# ProtoPass.net
KiCad netlist of a schematic drawn in EAGLE
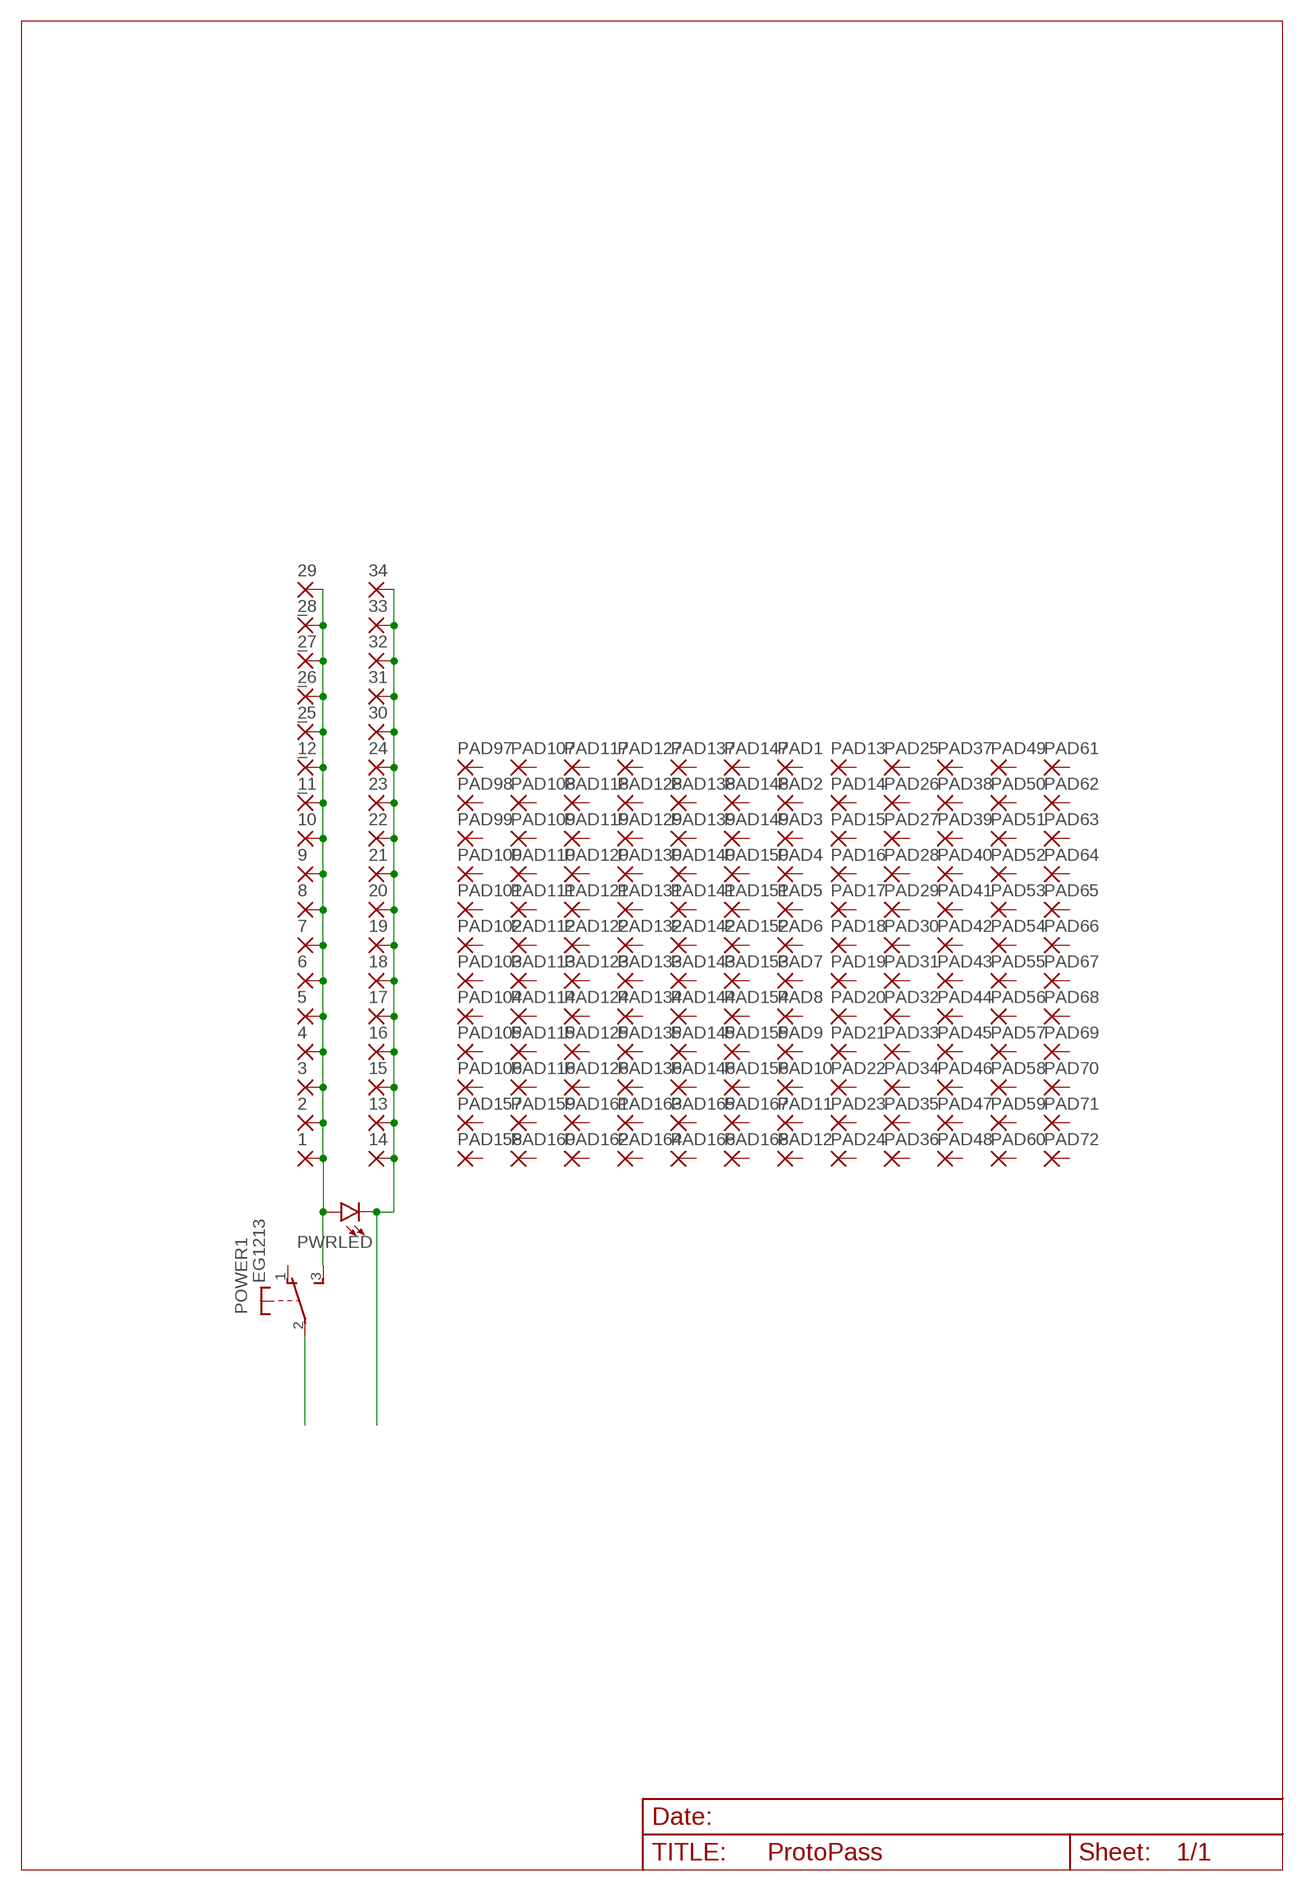
[diagram p0: schematic, sheet 1]

(export (version "E")
  (design (tool "Eeschema 10.0.6"))
  (components
    (comp (ref "1")
      (value "1,6/0,9")
      (footprint "eagle-import:1,6_0,9")
      (libsource (lib "eagle-import") (part "1,6/0,9"))
    )
    (comp (ref "2")
      (value "1,6/0,9")
      (footprint "eagle-import:1,6_0,9")
      (libsource (lib "eagle-import") (part "1,6/0,9"))
    )
    (comp (ref "3")
      (value "1,6/0,9")
      (footprint "eagle-import:1,6_0,9")
      (libsource (lib "eagle-import") (part "1,6/0,9"))
    )
    (comp (ref "4")
      (value "1,6/0,9")
      (footprint "eagle-import:1,6_0,9")
      (libsource (lib "eagle-import") (part "1,6/0,9"))
    )
    (comp (ref "5")
      (value "1,6/0,9")
      (footprint "eagle-import:1,6_0,9")
      (libsource (lib "eagle-import") (part "1,6/0,9"))
    )
    (comp (ref "6")
      (value "1,6/0,9")
      (footprint "eagle-import:1,6_0,9")
      (libsource (lib "eagle-import") (part "1,6/0,9"))
    )
    (comp (ref "7")
      (value "1,6/0,9")
      (footprint "eagle-import:1,6_0,9")
      (libsource (lib "eagle-import") (part "1,6/0,9"))
    )
    (comp (ref "8")
      (value "1,6/0,9")
      (footprint "eagle-import:1,6_0,9")
      (libsource (lib "eagle-import") (part "1,6/0,9"))
    )
    (comp (ref "9")
      (value "1,6/0,9")
      (footprint "eagle-import:1,6_0,9")
      (libsource (lib "eagle-import") (part "1,6/0,9"))
    )
    (comp (ref "10")
      (value "1,6/0,9")
      (footprint "eagle-import:1,6_0,9")
      (libsource (lib "eagle-import") (part "1,6/0,9"))
    )
    (comp (ref "11")
      (value "1,6/0,9")
      (footprint "eagle-import:1,6_0,9")
      (libsource (lib "eagle-import") (part "1,6/0,9"))
    )
    (comp (ref "12")
      (value "_")
      (footprint "eagle-import:1,6_0,9")
      (libsource (lib "eagle-import") (part "1,6/0,9"))
    )
    (comp (ref "13")
      (value "1,6/0,9")
      (footprint "eagle-import:1,6_0,9")
      (libsource (lib "eagle-import") (part "1,6/0,9"))
    )
    (comp (ref "14")
      (value "1,6/0,9")
      (footprint "eagle-import:1,6_0,9")
      (libsource (lib "eagle-import") (part "1,6/0,9"))
    )
    (comp (ref "15")
      (value "1,6/0,9")
      (footprint "eagle-import:1,6_0,9")
      (libsource (lib "eagle-import") (part "1,6/0,9"))
    )
    (comp (ref "16")
      (value "1,6/0,9")
      (footprint "eagle-import:1,6_0,9")
      (libsource (lib "eagle-import") (part "1,6/0,9"))
    )
    (comp (ref "17")
      (value "1,6/0,9")
      (footprint "eagle-import:1,6_0,9")
      (libsource (lib "eagle-import") (part "1,6/0,9"))
    )
    (comp (ref "18")
      (value "1,6/0,9")
      (footprint "eagle-import:1,6_0,9")
      (libsource (lib "eagle-import") (part "1,6/0,9"))
    )
    (comp (ref "19")
      (value "1,6/0,9")
      (footprint "eagle-import:1,6_0,9")
      (libsource (lib "eagle-import") (part "1,6/0,9"))
    )
    (comp (ref "20")
      (value "1,6/0,9")
      (footprint "eagle-import:1,6_0,9")
      (libsource (lib "eagle-import") (part "1,6/0,9"))
    )
    (comp (ref "21")
      (value "1,6/0,9")
      (footprint "eagle-import:1,6_0,9")
      (libsource (lib "eagle-import") (part "1,6/0,9"))
    )
    (comp (ref "22")
      (value "1,6/0,9")
      (footprint "eagle-import:1,6_0,9")
      (libsource (lib "eagle-import") (part "1,6/0,9"))
    )
    (comp (ref "23")
      (value "1,6/0,9")
      (footprint "eagle-import:1,6_0,9")
      (libsource (lib "eagle-import") (part "1,6/0,9"))
    )
    (comp (ref "24")
      (value "1,6/0,9")
      (footprint "eagle-import:1,6_0,9")
      (libsource (lib "eagle-import") (part "1,6/0,9"))
    )
    (comp (ref "25")
      (value "_")
      (footprint "eagle-import:1,6_0,9")
      (libsource (lib "eagle-import") (part "1,6/0,9"))
    )
    (comp (ref "26")
      (value "_")
      (footprint "eagle-import:1,6_0,9")
      (libsource (lib "eagle-import") (part "1,6/0,9"))
    )
    (comp (ref "27")
      (value "_")
      (footprint "eagle-import:1,6_0,9")
      (libsource (lib "eagle-import") (part "1,6/0,9"))
    )
    (comp (ref "28")
      (value "_")
      (footprint "eagle-import:1,6_0,9")
      (libsource (lib "eagle-import") (part "1,6/0,9"))
    )
    (comp (ref "29")
      (value "_")
      (footprint "eagle-import:1,6_0,9")
      (libsource (lib "eagle-import") (part "1,6/0,9"))
    )
    (comp (ref "30")
      (value "1,6/0,9")
      (footprint "eagle-import:1,6_0,9")
      (libsource (lib "eagle-import") (part "1,6/0,9"))
    )
    (comp (ref "31")
      (value "1,6/0,9")
      (footprint "eagle-import:1,6_0,9")
      (libsource (lib "eagle-import") (part "1,6/0,9"))
    )
    (comp (ref "32")
      (value "1,6/0,9")
      (footprint "eagle-import:1,6_0,9")
      (libsource (lib "eagle-import") (part "1,6/0,9"))
    )
    (comp (ref "33")
      (value "1,6/0,9")
      (footprint "eagle-import:1,6_0,9")
      (libsource (lib "eagle-import") (part "1,6/0,9"))
    )
    (comp (ref "34")
      (value "1,6/0,9")
      (footprint "eagle-import:1,6_0,9")
      (libsource (lib "eagle-import") (part "1,6/0,9"))
    )
    (comp (ref "PAD1")
      (value "1,6/0,9")
      (footprint "eagle-import:1,6_0,9")
      (libsource (lib "eagle-import") (part "1,6/0,9"))
    )
    (comp (ref "PAD2")
      (value "1,6/0,9")
      (footprint "eagle-import:1,6_0,9")
      (libsource (lib "eagle-import") (part "1,6/0,9"))
    )
    (comp (ref "PAD3")
      (value "1,6/0,9")
      (footprint "eagle-import:1,6_0,9")
      (libsource (lib "eagle-import") (part "1,6/0,9"))
    )
    (comp (ref "PAD4")
      (value "1,6/0,9")
      (footprint "eagle-import:1,6_0,9")
      (libsource (lib "eagle-import") (part "1,6/0,9"))
    )
    (comp (ref "PAD5")
      (value "1,6/0,9")
      (footprint "eagle-import:1,6_0,9")
      (libsource (lib "eagle-import") (part "1,6/0,9"))
    )
    (comp (ref "PAD6")
      (value "1,6/0,9")
      (footprint "eagle-import:1,6_0,9")
      (libsource (lib "eagle-import") (part "1,6/0,9"))
    )
    (comp (ref "PAD7")
      (value "1,6/0,9")
      (footprint "eagle-import:1,6_0,9")
      (libsource (lib "eagle-import") (part "1,6/0,9"))
    )
    (comp (ref "PAD8")
      (value "1,6/0,9")
      (footprint "eagle-import:1,6_0,9")
      (libsource (lib "eagle-import") (part "1,6/0,9"))
    )
    (comp (ref "PAD9")
      (value "1,6/0,9")
      (footprint "eagle-import:1,6_0,9")
      (libsource (lib "eagle-import") (part "1,6/0,9"))
    )
    (comp (ref "PAD10")
      (value "1,6/0,9")
      (footprint "eagle-import:1,6_0,9")
      (libsource (lib "eagle-import") (part "1,6/0,9"))
    )
    (comp (ref "PAD11")
      (value "1,6/0,9")
      (footprint "eagle-import:1,6_0,9")
      (libsource (lib "eagle-import") (part "1,6/0,9"))
    )
    (comp (ref "PAD12")
      (value "1,6/0,9")
      (footprint "eagle-import:1,6_0,9")
      (libsource (lib "eagle-import") (part "1,6/0,9"))
    )
    (comp (ref "PAD13")
      (value "1,6/0,9")
      (footprint "eagle-import:1,6_0,9")
      (libsource (lib "eagle-import") (part "1,6/0,9"))
    )
    (comp (ref "PAD14")
      (value "1,6/0,9")
      (footprint "eagle-import:1,6_0,9")
      (libsource (lib "eagle-import") (part "1,6/0,9"))
    )
    (comp (ref "PAD15")
      (value "1,6/0,9")
      (footprint "eagle-import:1,6_0,9")
      (libsource (lib "eagle-import") (part "1,6/0,9"))
    )
    (comp (ref "PAD16")
      (value "1,6/0,9")
      (footprint "eagle-import:1,6_0,9")
      (libsource (lib "eagle-import") (part "1,6/0,9"))
    )
    (comp (ref "PAD17")
      (value "1,6/0,9")
      (footprint "eagle-import:1,6_0,9")
      (libsource (lib "eagle-import") (part "1,6/0,9"))
    )
    (comp (ref "PAD18")
      (value "1,6/0,9")
      (footprint "eagle-import:1,6_0,9")
      (libsource (lib "eagle-import") (part "1,6/0,9"))
    )
    (comp (ref "PAD19")
      (value "1,6/0,9")
      (footprint "eagle-import:1,6_0,9")
      (libsource (lib "eagle-import") (part "1,6/0,9"))
    )
    (comp (ref "PAD20")
      (value "1,6/0,9")
      (footprint "eagle-import:1,6_0,9")
      (libsource (lib "eagle-import") (part "1,6/0,9"))
    )
    (comp (ref "PAD21")
      (value "1,6/0,9")
      (footprint "eagle-import:1,6_0,9")
      (libsource (lib "eagle-import") (part "1,6/0,9"))
    )
    (comp (ref "PAD22")
      (value "1,6/0,9")
      (footprint "eagle-import:1,6_0,9")
      (libsource (lib "eagle-import") (part "1,6/0,9"))
    )
    (comp (ref "PAD23")
      (value "1,6/0,9")
      (footprint "eagle-import:1,6_0,9")
      (libsource (lib "eagle-import") (part "1,6/0,9"))
    )
    (comp (ref "PAD24")
      (value "1,6/0,9")
      (footprint "eagle-import:1,6_0,9")
      (libsource (lib "eagle-import") (part "1,6/0,9"))
    )
    (comp (ref "PAD25")
      (value "1,6/0,9")
      (footprint "eagle-import:1,6_0,9")
      (libsource (lib "eagle-import") (part "1,6/0,9"))
    )
    (comp (ref "PAD26")
      (value "1,6/0,9")
      (footprint "eagle-import:1,6_0,9")
      (libsource (lib "eagle-import") (part "1,6/0,9"))
    )
    (comp (ref "PAD27")
      (value "1,6/0,9")
      (footprint "eagle-import:1,6_0,9")
      (libsource (lib "eagle-import") (part "1,6/0,9"))
    )
    (comp (ref "PAD28")
      (value "1,6/0,9")
      (footprint "eagle-import:1,6_0,9")
      (libsource (lib "eagle-import") (part "1,6/0,9"))
    )
    (comp (ref "PAD29")
      (value "1,6/0,9")
      (footprint "eagle-import:1,6_0,9")
      (libsource (lib "eagle-import") (part "1,6/0,9"))
    )
    (comp (ref "PAD30")
      (value "1,6/0,9")
      (footprint "eagle-import:1,6_0,9")
      (libsource (lib "eagle-import") (part "1,6/0,9"))
    )
    (comp (ref "PAD31")
      (value "1,6/0,9")
      (footprint "eagle-import:1,6_0,9")
      (libsource (lib "eagle-import") (part "1,6/0,9"))
    )
    (comp (ref "PAD32")
      (value "1,6/0,9")
      (footprint "eagle-import:1,6_0,9")
      (libsource (lib "eagle-import") (part "1,6/0,9"))
    )
    (comp (ref "PAD33")
      (value "1,6/0,9")
      (footprint "eagle-import:1,6_0,9")
      (libsource (lib "eagle-import") (part "1,6/0,9"))
    )
    (comp (ref "PAD34")
      (value "1,6/0,9")
      (footprint "eagle-import:1,6_0,9")
      (libsource (lib "eagle-import") (part "1,6/0,9"))
    )
    (comp (ref "PAD35")
      (value "1,6/0,9")
      (footprint "eagle-import:1,6_0,9")
      (libsource (lib "eagle-import") (part "1,6/0,9"))
    )
    (comp (ref "PAD36")
      (value "1,6/0,9")
      (footprint "eagle-import:1,6_0,9")
      (libsource (lib "eagle-import") (part "1,6/0,9"))
    )
    (comp (ref "PAD37")
      (value "1,6/0,9")
      (footprint "eagle-import:1,6_0,9")
      (libsource (lib "eagle-import") (part "1,6/0,9"))
    )
    (comp (ref "PAD38")
      (value "1,6/0,9")
      (footprint "eagle-import:1,6_0,9")
      (libsource (lib "eagle-import") (part "1,6/0,9"))
    )
    (comp (ref "PAD39")
      (value "1,6/0,9")
      (footprint "eagle-import:1,6_0,9")
      (libsource (lib "eagle-import") (part "1,6/0,9"))
    )
    (comp (ref "PAD40")
      (value "1,6/0,9")
      (footprint "eagle-import:1,6_0,9")
      (libsource (lib "eagle-import") (part "1,6/0,9"))
    )
    (comp (ref "PAD41")
      (value "1,6/0,9")
      (footprint "eagle-import:1,6_0,9")
      (libsource (lib "eagle-import") (part "1,6/0,9"))
    )
    (comp (ref "PAD42")
      (value "1,6/0,9")
      (footprint "eagle-import:1,6_0,9")
      (libsource (lib "eagle-import") (part "1,6/0,9"))
    )
    (comp (ref "PAD43")
      (value "1,6/0,9")
      (footprint "eagle-import:1,6_0,9")
      (libsource (lib "eagle-import") (part "1,6/0,9"))
    )
    (comp (ref "PAD44")
      (value "1,6/0,9")
      (footprint "eagle-import:1,6_0,9")
      (libsource (lib "eagle-import") (part "1,6/0,9"))
    )
    (comp (ref "PAD45")
      (value "1,6/0,9")
      (footprint "eagle-import:1,6_0,9")
      (libsource (lib "eagle-import") (part "1,6/0,9"))
    )
    (comp (ref "PAD46")
      (value "1,6/0,9")
      (footprint "eagle-import:1,6_0,9")
      (libsource (lib "eagle-import") (part "1,6/0,9"))
    )
    (comp (ref "PAD47")
      (value "1,6/0,9")
      (footprint "eagle-import:1,6_0,9")
      (libsource (lib "eagle-import") (part "1,6/0,9"))
    )
    (comp (ref "PAD48")
      (value "1,6/0,9")
      (footprint "eagle-import:1,6_0,9")
      (libsource (lib "eagle-import") (part "1,6/0,9"))
    )
    (comp (ref "PAD49")
      (value "1,6/0,9")
      (footprint "eagle-import:1,6_0,9")
      (libsource (lib "eagle-import") (part "1,6/0,9"))
    )
    (comp (ref "PAD50")
      (value "1,6/0,9")
      (footprint "eagle-import:1,6_0,9")
      (libsource (lib "eagle-import") (part "1,6/0,9"))
    )
    (comp (ref "PAD51")
      (value "1,6/0,9")
      (footprint "eagle-import:1,6_0,9")
      (libsource (lib "eagle-import") (part "1,6/0,9"))
    )
    (comp (ref "PAD52")
      (value "1,6/0,9")
      (footprint "eagle-import:1,6_0,9")
      (libsource (lib "eagle-import") (part "1,6/0,9"))
    )
    (comp (ref "PAD53")
      (value "1,6/0,9")
      (footprint "eagle-import:1,6_0,9")
      (libsource (lib "eagle-import") (part "1,6/0,9"))
    )
    (comp (ref "PAD54")
      (value "1,6/0,9")
      (footprint "eagle-import:1,6_0,9")
      (libsource (lib "eagle-import") (part "1,6/0,9"))
    )
    (comp (ref "PAD55")
      (value "1,6/0,9")
      (footprint "eagle-import:1,6_0,9")
      (libsource (lib "eagle-import") (part "1,6/0,9"))
    )
    (comp (ref "PAD56")
      (value "1,6/0,9")
      (footprint "eagle-import:1,6_0,9")
      (libsource (lib "eagle-import") (part "1,6/0,9"))
    )
    (comp (ref "PAD57")
      (value "1,6/0,9")
      (footprint "eagle-import:1,6_0,9")
      (libsource (lib "eagle-import") (part "1,6/0,9"))
    )
    (comp (ref "PAD58")
      (value "1,6/0,9")
      (footprint "eagle-import:1,6_0,9")
      (libsource (lib "eagle-import") (part "1,6/0,9"))
    )
    (comp (ref "PAD59")
      (value "1,6/0,9")
      (footprint "eagle-import:1,6_0,9")
      (libsource (lib "eagle-import") (part "1,6/0,9"))
    )
    (comp (ref "PAD60")
      (value "1,6/0,9")
      (footprint "eagle-import:1,6_0,9")
      (libsource (lib "eagle-import") (part "1,6/0,9"))
    )
    (comp (ref "PAD61")
      (value "1,6/0,9")
      (footprint "eagle-import:1,6_0,9")
      (libsource (lib "eagle-import") (part "1,6/0,9"))
    )
    (comp (ref "PAD62")
      (value "1,6/0,9")
      (footprint "eagle-import:1,6_0,9")
      (libsource (lib "eagle-import") (part "1,6/0,9"))
    )
    (comp (ref "PAD63")
      (value "1,6/0,9")
      (footprint "eagle-import:1,6_0,9")
      (libsource (lib "eagle-import") (part "1,6/0,9"))
    )
    (comp (ref "PAD64")
      (value "1,6/0,9")
      (footprint "eagle-import:1,6_0,9")
      (libsource (lib "eagle-import") (part "1,6/0,9"))
    )
    (comp (ref "PAD65")
      (value "1,6/0,9")
      (footprint "eagle-import:1,6_0,9")
      (libsource (lib "eagle-import") (part "1,6/0,9"))
    )
    (comp (ref "PAD66")
      (value "1,6/0,9")
      (footprint "eagle-import:1,6_0,9")
      (libsource (lib "eagle-import") (part "1,6/0,9"))
    )
    (comp (ref "PAD67")
      (value "1,6/0,9")
      (footprint "eagle-import:1,6_0,9")
      (libsource (lib "eagle-import") (part "1,6/0,9"))
    )
    (comp (ref "PAD68")
      (value "1,6/0,9")
      (footprint "eagle-import:1,6_0,9")
      (libsource (lib "eagle-import") (part "1,6/0,9"))
    )
    (comp (ref "PAD69")
      (value "1,6/0,9")
      (footprint "eagle-import:1,6_0,9")
      (libsource (lib "eagle-import") (part "1,6/0,9"))
    )
    (comp (ref "PAD70")
      (value "1,6/0,9")
      (footprint "eagle-import:1,6_0,9")
      (libsource (lib "eagle-import") (part "1,6/0,9"))
    )
    (comp (ref "PAD71")
      (value "1,6/0,9")
      (footprint "eagle-import:1,6_0,9")
      (libsource (lib "eagle-import") (part "1,6/0,9"))
    )
    (comp (ref "PAD72")
      (value "1,6/0,9")
      (footprint "eagle-import:1,6_0,9")
      (libsource (lib "eagle-import") (part "1,6/0,9"))
    )
    (comp (ref "PAD97")
      (value "1,6/0,9")
      (footprint "eagle-import:1,6_0,9")
      (libsource (lib "eagle-import") (part "1,6/0,9"))
    )
    (comp (ref "PAD98")
      (value "1,6/0,9")
      (footprint "eagle-import:1,6_0,9")
      (libsource (lib "eagle-import") (part "1,6/0,9"))
    )
    (comp (ref "PAD99")
      (value "1,6/0,9")
      (footprint "eagle-import:1,6_0,9")
      (libsource (lib "eagle-import") (part "1,6/0,9"))
    )
    (comp (ref "PAD100")
      (value "1,6/0,9")
      (footprint "eagle-import:1,6_0,9")
      (libsource (lib "eagle-import") (part "1,6/0,9"))
    )
    (comp (ref "PAD101")
      (value "1,6/0,9")
      (footprint "eagle-import:1,6_0,9")
      (libsource (lib "eagle-import") (part "1,6/0,9"))
    )
    (comp (ref "PAD102")
      (value "1,6/0,9")
      (footprint "eagle-import:1,6_0,9")
      (libsource (lib "eagle-import") (part "1,6/0,9"))
    )
    (comp (ref "PAD103")
      (value "1,6/0,9")
      (footprint "eagle-import:1,6_0,9")
      (libsource (lib "eagle-import") (part "1,6/0,9"))
    )
    (comp (ref "PAD104")
      (value "1,6/0,9")
      (footprint "eagle-import:1,6_0,9")
      (libsource (lib "eagle-import") (part "1,6/0,9"))
    )
    (comp (ref "PAD105")
      (value "1,6/0,9")
      (footprint "eagle-import:1,6_0,9")
      (libsource (lib "eagle-import") (part "1,6/0,9"))
    )
    (comp (ref "PAD106")
      (value "1,6/0,9")
      (footprint "eagle-import:1,6_0,9")
      (libsource (lib "eagle-import") (part "1,6/0,9"))
    )
    (comp (ref "PAD107")
      (value "1,6/0,9")
      (footprint "eagle-import:1,6_0,9")
      (libsource (lib "eagle-import") (part "1,6/0,9"))
    )
    (comp (ref "PAD108")
      (value "1,6/0,9")
      (footprint "eagle-import:1,6_0,9")
      (libsource (lib "eagle-import") (part "1,6/0,9"))
    )
    (comp (ref "PAD109")
      (value "1,6/0,9")
      (footprint "eagle-import:1,6_0,9")
      (libsource (lib "eagle-import") (part "1,6/0,9"))
    )
    (comp (ref "PAD110")
      (value "1,6/0,9")
      (footprint "eagle-import:1,6_0,9")
      (libsource (lib "eagle-import") (part "1,6/0,9"))
    )
    (comp (ref "PAD111")
      (value "1,6/0,9")
      (footprint "eagle-import:1,6_0,9")
      (libsource (lib "eagle-import") (part "1,6/0,9"))
    )
    (comp (ref "PAD112")
      (value "1,6/0,9")
      (footprint "eagle-import:1,6_0,9")
      (libsource (lib "eagle-import") (part "1,6/0,9"))
    )
    (comp (ref "PAD113")
      (value "1,6/0,9")
      (footprint "eagle-import:1,6_0,9")
      (libsource (lib "eagle-import") (part "1,6/0,9"))
    )
    (comp (ref "PAD114")
      (value "1,6/0,9")
      (footprint "eagle-import:1,6_0,9")
      (libsource (lib "eagle-import") (part "1,6/0,9"))
    )
    (comp (ref "PAD115")
      (value "1,6/0,9")
      (footprint "eagle-import:1,6_0,9")
      (libsource (lib "eagle-import") (part "1,6/0,9"))
    )
    (comp (ref "PAD116")
      (value "1,6/0,9")
      (footprint "eagle-import:1,6_0,9")
      (libsource (lib "eagle-import") (part "1,6/0,9"))
    )
    (comp (ref "PAD117")
      (value "1,6/0,9")
      (footprint "eagle-import:1,6_0,9")
      (libsource (lib "eagle-import") (part "1,6/0,9"))
    )
    (comp (ref "PAD118")
      (value "1,6/0,9")
      (footprint "eagle-import:1,6_0,9")
      (libsource (lib "eagle-import") (part "1,6/0,9"))
    )
    (comp (ref "PAD119")
      (value "1,6/0,9")
      (footprint "eagle-import:1,6_0,9")
      (libsource (lib "eagle-import") (part "1,6/0,9"))
    )
    (comp (ref "PAD120")
      (value "1,6/0,9")
      (footprint "eagle-import:1,6_0,9")
      (libsource (lib "eagle-import") (part "1,6/0,9"))
    )
    (comp (ref "PAD121")
      (value "1,6/0,9")
      (footprint "eagle-import:1,6_0,9")
      (libsource (lib "eagle-import") (part "1,6/0,9"))
    )
    (comp (ref "PAD122")
      (value "1,6/0,9")
      (footprint "eagle-import:1,6_0,9")
      (libsource (lib "eagle-import") (part "1,6/0,9"))
    )
    (comp (ref "PAD123")
      (value "1,6/0,9")
      (footprint "eagle-import:1,6_0,9")
      (libsource (lib "eagle-import") (part "1,6/0,9"))
    )
    (comp (ref "PAD124")
      (value "1,6/0,9")
      (footprint "eagle-import:1,6_0,9")
      (libsource (lib "eagle-import") (part "1,6/0,9"))
    )
    (comp (ref "PAD125")
      (value "1,6/0,9")
      (footprint "eagle-import:1,6_0,9")
      (libsource (lib "eagle-import") (part "1,6/0,9"))
    )
    (comp (ref "PAD126")
      (value "1,6/0,9")
      (footprint "eagle-import:1,6_0,9")
      (libsource (lib "eagle-import") (part "1,6/0,9"))
    )
    (comp (ref "PAD127")
      (value "1,6/0,9")
      (footprint "eagle-import:1,6_0,9")
      (libsource (lib "eagle-import") (part "1,6/0,9"))
    )
    (comp (ref "PAD128")
      (value "1,6/0,9")
      (footprint "eagle-import:1,6_0,9")
      (libsource (lib "eagle-import") (part "1,6/0,9"))
    )
    (comp (ref "PAD129")
      (value "1,6/0,9")
      (footprint "eagle-import:1,6_0,9")
      (libsource (lib "eagle-import") (part "1,6/0,9"))
    )
    (comp (ref "PAD130")
      (value "1,6/0,9")
      (footprint "eagle-import:1,6_0,9")
      (libsource (lib "eagle-import") (part "1,6/0,9"))
    )
    (comp (ref "PAD131")
      (value "1,6/0,9")
      (footprint "eagle-import:1,6_0,9")
      (libsource (lib "eagle-import") (part "1,6/0,9"))
    )
    (comp (ref "PAD132")
      (value "1,6/0,9")
      (footprint "eagle-import:1,6_0,9")
      (libsource (lib "eagle-import") (part "1,6/0,9"))
    )
    (comp (ref "PAD133")
      (value "1,6/0,9")
      (footprint "eagle-import:1,6_0,9")
      (libsource (lib "eagle-import") (part "1,6/0,9"))
    )
    (comp (ref "PAD134")
      (value "1,6/0,9")
      (footprint "eagle-import:1,6_0,9")
      (libsource (lib "eagle-import") (part "1,6/0,9"))
    )
    (comp (ref "PAD135")
      (value "1,6/0,9")
      (footprint "eagle-import:1,6_0,9")
      (libsource (lib "eagle-import") (part "1,6/0,9"))
    )
    (comp (ref "PAD136")
      (value "1,6/0,9")
      (footprint "eagle-import:1,6_0,9")
      (libsource (lib "eagle-import") (part "1,6/0,9"))
    )
    (comp (ref "PAD137")
      (value "1,6/0,9")
      (footprint "eagle-import:1,6_0,9")
      (libsource (lib "eagle-import") (part "1,6/0,9"))
    )
    (comp (ref "PAD138")
      (value "1,6/0,9")
      (footprint "eagle-import:1,6_0,9")
      (libsource (lib "eagle-import") (part "1,6/0,9"))
    )
    (comp (ref "PAD139")
      (value "1,6/0,9")
      (footprint "eagle-import:1,6_0,9")
      (libsource (lib "eagle-import") (part "1,6/0,9"))
    )
    (comp (ref "PAD140")
      (value "1,6/0,9")
      (footprint "eagle-import:1,6_0,9")
      (libsource (lib "eagle-import") (part "1,6/0,9"))
    )
    (comp (ref "PAD141")
      (value "1,6/0,9")
      (footprint "eagle-import:1,6_0,9")
      (libsource (lib "eagle-import") (part "1,6/0,9"))
    )
    (comp (ref "PAD142")
      (value "1,6/0,9")
      (footprint "eagle-import:1,6_0,9")
      (libsource (lib "eagle-import") (part "1,6/0,9"))
    )
    (comp (ref "PAD143")
      (value "1,6/0,9")
      (footprint "eagle-import:1,6_0,9")
      (libsource (lib "eagle-import") (part "1,6/0,9"))
    )
    (comp (ref "PAD144")
      (value "1,6/0,9")
      (footprint "eagle-import:1,6_0,9")
      (libsource (lib "eagle-import") (part "1,6/0,9"))
    )
    (comp (ref "PAD145")
      (value "1,6/0,9")
      (footprint "eagle-import:1,6_0,9")
      (libsource (lib "eagle-import") (part "1,6/0,9"))
    )
    (comp (ref "PAD146")
      (value "1,6/0,9")
      (footprint "eagle-import:1,6_0,9")
      (libsource (lib "eagle-import") (part "1,6/0,9"))
    )
    (comp (ref "PAD147")
      (value "1,6/0,9")
      (footprint "eagle-import:1,6_0,9")
      (libsource (lib "eagle-import") (part "1,6/0,9"))
    )
    (comp (ref "PAD148")
      (value "1,6/0,9")
      (footprint "eagle-import:1,6_0,9")
      (libsource (lib "eagle-import") (part "1,6/0,9"))
    )
    (comp (ref "PAD149")
      (value "1,6/0,9")
      (footprint "eagle-import:1,6_0,9")
      (libsource (lib "eagle-import") (part "1,6/0,9"))
    )
    (comp (ref "PAD150")
      (value "1,6/0,9")
      (footprint "eagle-import:1,6_0,9")
      (libsource (lib "eagle-import") (part "1,6/0,9"))
    )
    (comp (ref "PAD151")
      (value "1,6/0,9")
      (footprint "eagle-import:1,6_0,9")
      (libsource (lib "eagle-import") (part "1,6/0,9"))
    )
    (comp (ref "PAD152")
      (value "1,6/0,9")
      (footprint "eagle-import:1,6_0,9")
      (libsource (lib "eagle-import") (part "1,6/0,9"))
    )
    (comp (ref "PAD153")
      (value "1,6/0,9")
      (footprint "eagle-import:1,6_0,9")
      (libsource (lib "eagle-import") (part "1,6/0,9"))
    )
    (comp (ref "PAD154")
      (value "1,6/0,9")
      (footprint "eagle-import:1,6_0,9")
      (libsource (lib "eagle-import") (part "1,6/0,9"))
    )
    (comp (ref "PAD155")
      (value "1,6/0,9")
      (footprint "eagle-import:1,6_0,9")
      (libsource (lib "eagle-import") (part "1,6/0,9"))
    )
    (comp (ref "PAD156")
      (value "1,6/0,9")
      (footprint "eagle-import:1,6_0,9")
      (libsource (lib "eagle-import") (part "1,6/0,9"))
    )
    (comp (ref "PAD157")
      (value "1,6/0,9")
      (footprint "eagle-import:1,6_0,9")
      (libsource (lib "eagle-import") (part "1,6/0,9"))
    )
    (comp (ref "PAD158")
      (value "1,6/0,9")
      (footprint "eagle-import:1,6_0,9")
      (libsource (lib "eagle-import") (part "1,6/0,9"))
    )
    (comp (ref "PAD159")
      (value "1,6/0,9")
      (footprint "eagle-import:1,6_0,9")
      (libsource (lib "eagle-import") (part "1,6/0,9"))
    )
    (comp (ref "PAD160")
      (value "1,6/0,9")
      (footprint "eagle-import:1,6_0,9")
      (libsource (lib "eagle-import") (part "1,6/0,9"))
    )
    (comp (ref "PAD161")
      (value "1,6/0,9")
      (footprint "eagle-import:1,6_0,9")
      (libsource (lib "eagle-import") (part "1,6/0,9"))
    )
    (comp (ref "PAD162")
      (value "1,6/0,9")
      (footprint "eagle-import:1,6_0,9")
      (libsource (lib "eagle-import") (part "1,6/0,9"))
    )
    (comp (ref "PAD163")
      (value "1,6/0,9")
      (footprint "eagle-import:1,6_0,9")
      (libsource (lib "eagle-import") (part "1,6/0,9"))
    )
    (comp (ref "PAD164")
      (value "1,6/0,9")
      (footprint "eagle-import:1,6_0,9")
      (libsource (lib "eagle-import") (part "1,6/0,9"))
    )
    (comp (ref "PAD165")
      (value "1,6/0,9")
      (footprint "eagle-import:1,6_0,9")
      (libsource (lib "eagle-import") (part "1,6/0,9"))
    )
    (comp (ref "PAD166")
      (value "1,6/0,9")
      (footprint "eagle-import:1,6_0,9")
      (libsource (lib "eagle-import") (part "1,6/0,9"))
    )
    (comp (ref "PAD167")
      (value "1,6/0,9")
      (footprint "eagle-import:1,6_0,9")
      (libsource (lib "eagle-import") (part "1,6/0,9"))
    )
    (comp (ref "PAD168")
      (value "1,6/0,9")
      (footprint "eagle-import:1,6_0,9")
      (libsource (lib "eagle-import") (part "1,6/0,9"))
    )
    (comp (ref "POWER")
      (value "EG1213")
      (footprint "eagle-import:EG1213")
      (libsource (lib "eagle-import") (part "EG1213"))
    )
    (comp (ref "PWRLED")
      (value "LED5MM")
      (footprint "eagle-import:LED_5MM")
      (libsource (lib "eagle-import") (part "LED5MM"))
    )
  )
  (nets
    (net (code "1") (name "Net-(1-P)") (class "Default")
      (node (ref "1") (pin "1") (pinfunction "P_1") (pintype "passive"))
      (node (ref "10") (pin "1") (pinfunction "P_1") (pintype "passive"))
      (node (ref "11") (pin "1") (pinfunction "P_1") (pintype "passive"))
      (node (ref "12") (pin "1") (pinfunction "P_1") (pintype "passive"))
      (node (ref "2") (pin "1") (pinfunction "P_1") (pintype "passive"))
      (node (ref "25") (pin "1") (pinfunction "P_1") (pintype "passive"))
      (node (ref "26") (pin "1") (pinfunction "P_1") (pintype "passive"))
      (node (ref "27") (pin "1") (pinfunction "P_1") (pintype "passive"))
      (node (ref "28") (pin "1") (pinfunction "P_1") (pintype "passive"))
      (node (ref "29") (pin "1") (pinfunction "P_1") (pintype "passive"))
      (node (ref "3") (pin "1") (pinfunction "P_1") (pintype "passive"))
      (node (ref "4") (pin "1") (pinfunction "P_1") (pintype "passive"))
      (node (ref "5") (pin "1") (pinfunction "P_1") (pintype "passive"))
      (node (ref "6") (pin "1") (pinfunction "P_1") (pintype "passive"))
      (node (ref "7") (pin "1") (pinfunction "P_1") (pintype "passive"))
      (node (ref "8") (pin "1") (pinfunction "P_1") (pintype "passive"))
      (node (ref "9") (pin "1") (pinfunction "P_1") (pintype "passive"))
      (node (ref "POWER") (pin "3") (pinfunction "S_3") (pintype "passive"))
      (node (ref "PWRLED") (pin "A") (pinfunction "A_A") (pintype "passive"))
    )
    (net (code "2") (name "Net-(13-P)") (class "Default")
      (node (ref "13") (pin "1") (pinfunction "P_1") (pintype "passive"))
      (node (ref "14") (pin "1") (pinfunction "P_1") (pintype "passive"))
      (node (ref "15") (pin "1") (pinfunction "P_1") (pintype "passive"))
      (node (ref "16") (pin "1") (pinfunction "P_1") (pintype "passive"))
      (node (ref "17") (pin "1") (pinfunction "P_1") (pintype "passive"))
      (node (ref "18") (pin "1") (pinfunction "P_1") (pintype "passive"))
      (node (ref "19") (pin "1") (pinfunction "P_1") (pintype "passive"))
      (node (ref "20") (pin "1") (pinfunction "P_1") (pintype "passive"))
      (node (ref "21") (pin "1") (pinfunction "P_1") (pintype "passive"))
      (node (ref "22") (pin "1") (pinfunction "P_1") (pintype "passive"))
      (node (ref "23") (pin "1") (pinfunction "P_1") (pintype "passive"))
      (node (ref "24") (pin "1") (pinfunction "P_1") (pintype "passive"))
      (node (ref "30") (pin "1") (pinfunction "P_1") (pintype "passive"))
      (node (ref "31") (pin "1") (pinfunction "P_1") (pintype "passive"))
      (node (ref "32") (pin "1") (pinfunction "P_1") (pintype "passive"))
      (node (ref "33") (pin "1") (pinfunction "P_1") (pintype "passive"))
      (node (ref "34") (pin "1") (pinfunction "P_1") (pintype "passive"))
      (node (ref "PWRLED") (pin "K") (pinfunction "C_K") (pintype "passive"))
    )
    (net (code "3") (name "unconnected-(PAD1-P-Pad1)") (class "Default")
      (node (ref "PAD1") (pin "1") (pinfunction "P_1") (pintype "passive"))
    )
    (net (code "4") (name "unconnected-(PAD2-P-Pad1)") (class "Default")
      (node (ref "PAD2") (pin "1") (pinfunction "P_1") (pintype "passive"))
    )
    (net (code "5") (name "unconnected-(PAD3-P-Pad1)") (class "Default")
      (node (ref "PAD3") (pin "1") (pinfunction "P_1") (pintype "passive"))
    )
    (net (code "6") (name "unconnected-(PAD4-P-Pad1)") (class "Default")
      (node (ref "PAD4") (pin "1") (pinfunction "P_1") (pintype "passive"))
    )
    (net (code "7") (name "unconnected-(PAD5-P-Pad1)") (class "Default")
      (node (ref "PAD5") (pin "1") (pinfunction "P_1") (pintype "passive"))
    )
    (net (code "8") (name "unconnected-(PAD6-P-Pad1)") (class "Default")
      (node (ref "PAD6") (pin "1") (pinfunction "P_1") (pintype "passive"))
    )
    (net (code "9") (name "unconnected-(PAD7-P-Pad1)") (class "Default")
      (node (ref "PAD7") (pin "1") (pinfunction "P_1") (pintype "passive"))
    )
    (net (code "10") (name "unconnected-(PAD8-P-Pad1)") (class "Default")
      (node (ref "PAD8") (pin "1") (pinfunction "P_1") (pintype "passive"))
    )
    (net (code "11") (name "unconnected-(PAD9-P-Pad1)") (class "Default")
      (node (ref "PAD9") (pin "1") (pinfunction "P_1") (pintype "passive"))
    )
    (net (code "12") (name "unconnected-(PAD10-P-Pad1)") (class "Default")
      (node (ref "PAD10") (pin "1") (pinfunction "P_1") (pintype "passive"))
    )
    (net (code "13") (name "unconnected-(PAD11-P-Pad1)") (class "Default")
      (node (ref "PAD11") (pin "1") (pinfunction "P_1") (pintype "passive"))
    )
    (net (code "14") (name "unconnected-(PAD12-P-Pad1)") (class "Default")
      (node (ref "PAD12") (pin "1") (pinfunction "P_1") (pintype "passive"))
    )
    (net (code "15") (name "unconnected-(PAD13-P-Pad1)") (class "Default")
      (node (ref "PAD13") (pin "1") (pinfunction "P_1") (pintype "passive"))
    )
    (net (code "16") (name "unconnected-(PAD14-P-Pad1)") (class "Default")
      (node (ref "PAD14") (pin "1") (pinfunction "P_1") (pintype "passive"))
    )
    (net (code "17") (name "unconnected-(PAD15-P-Pad1)") (class "Default")
      (node (ref "PAD15") (pin "1") (pinfunction "P_1") (pintype "passive"))
    )
    (net (code "18") (name "unconnected-(PAD16-P-Pad1)") (class "Default")
      (node (ref "PAD16") (pin "1") (pinfunction "P_1") (pintype "passive"))
    )
    (net (code "19") (name "unconnected-(PAD17-P-Pad1)") (class "Default")
      (node (ref "PAD17") (pin "1") (pinfunction "P_1") (pintype "passive"))
    )
    (net (code "20") (name "unconnected-(PAD18-P-Pad1)") (class "Default")
      (node (ref "PAD18") (pin "1") (pinfunction "P_1") (pintype "passive"))
    )
    (net (code "21") (name "unconnected-(PAD19-P-Pad1)") (class "Default")
      (node (ref "PAD19") (pin "1") (pinfunction "P_1") (pintype "passive"))
    )
    (net (code "22") (name "unconnected-(PAD20-P-Pad1)") (class "Default")
      (node (ref "PAD20") (pin "1") (pinfunction "P_1") (pintype "passive"))
    )
    (net (code "23") (name "unconnected-(PAD21-P-Pad1)") (class "Default")
      (node (ref "PAD21") (pin "1") (pinfunction "P_1") (pintype "passive"))
    )
    (net (code "24") (name "unconnected-(PAD22-P-Pad1)") (class "Default")
      (node (ref "PAD22") (pin "1") (pinfunction "P_1") (pintype "passive"))
    )
    (net (code "25") (name "unconnected-(PAD23-P-Pad1)") (class "Default")
      (node (ref "PAD23") (pin "1") (pinfunction "P_1") (pintype "passive"))
    )
    (net (code "26") (name "unconnected-(PAD24-P-Pad1)") (class "Default")
      (node (ref "PAD24") (pin "1") (pinfunction "P_1") (pintype "passive"))
    )
    (net (code "27") (name "unconnected-(PAD25-P-Pad1)") (class "Default")
      (node (ref "PAD25") (pin "1") (pinfunction "P_1") (pintype "passive"))
    )
    (net (code "28") (name "unconnected-(PAD26-P-Pad1)") (class "Default")
      (node (ref "PAD26") (pin "1") (pinfunction "P_1") (pintype "passive"))
    )
    (net (code "29") (name "unconnected-(PAD27-P-Pad1)") (class "Default")
      (node (ref "PAD27") (pin "1") (pinfunction "P_1") (pintype "passive"))
    )
    (net (code "30") (name "unconnected-(PAD28-P-Pad1)") (class "Default")
      (node (ref "PAD28") (pin "1") (pinfunction "P_1") (pintype "passive"))
    )
    (net (code "31") (name "unconnected-(PAD29-P-Pad1)") (class "Default")
      (node (ref "PAD29") (pin "1") (pinfunction "P_1") (pintype "passive"))
    )
    (net (code "32") (name "unconnected-(PAD30-P-Pad1)") (class "Default")
      (node (ref "PAD30") (pin "1") (pinfunction "P_1") (pintype "passive"))
    )
    (net (code "33") (name "unconnected-(PAD31-P-Pad1)") (class "Default")
      (node (ref "PAD31") (pin "1") (pinfunction "P_1") (pintype "passive"))
    )
    (net (code "34") (name "unconnected-(PAD32-P-Pad1)") (class "Default")
      (node (ref "PAD32") (pin "1") (pinfunction "P_1") (pintype "passive"))
    )
    (net (code "35") (name "unconnected-(PAD33-P-Pad1)") (class "Default")
      (node (ref "PAD33") (pin "1") (pinfunction "P_1") (pintype "passive"))
    )
    (net (code "36") (name "unconnected-(PAD34-P-Pad1)") (class "Default")
      (node (ref "PAD34") (pin "1") (pinfunction "P_1") (pintype "passive"))
    )
    (net (code "37") (name "unconnected-(PAD35-P-Pad1)") (class "Default")
      (node (ref "PAD35") (pin "1") (pinfunction "P_1") (pintype "passive"))
    )
    (net (code "38") (name "unconnected-(PAD36-P-Pad1)") (class "Default")
      (node (ref "PAD36") (pin "1") (pinfunction "P_1") (pintype "passive"))
    )
    (net (code "39") (name "unconnected-(PAD37-P-Pad1)") (class "Default")
      (node (ref "PAD37") (pin "1") (pinfunction "P_1") (pintype "passive"))
    )
    (net (code "40") (name "unconnected-(PAD38-P-Pad1)") (class "Default")
      (node (ref "PAD38") (pin "1") (pinfunction "P_1") (pintype "passive"))
    )
    (net (code "41") (name "unconnected-(PAD39-P-Pad1)") (class "Default")
      (node (ref "PAD39") (pin "1") (pinfunction "P_1") (pintype "passive"))
    )
    (net (code "42") (name "unconnected-(PAD40-P-Pad1)") (class "Default")
      (node (ref "PAD40") (pin "1") (pinfunction "P_1") (pintype "passive"))
    )
    (net (code "43") (name "unconnected-(PAD41-P-Pad1)") (class "Default")
      (node (ref "PAD41") (pin "1") (pinfunction "P_1") (pintype "passive"))
    )
    (net (code "44") (name "unconnected-(PAD42-P-Pad1)") (class "Default")
      (node (ref "PAD42") (pin "1") (pinfunction "P_1") (pintype "passive"))
    )
    (net (code "45") (name "unconnected-(PAD43-P-Pad1)") (class "Default")
      (node (ref "PAD43") (pin "1") (pinfunction "P_1") (pintype "passive"))
    )
    (net (code "46") (name "unconnected-(PAD44-P-Pad1)") (class "Default")
      (node (ref "PAD44") (pin "1") (pinfunction "P_1") (pintype "passive"))
    )
    (net (code "47") (name "unconnected-(PAD45-P-Pad1)") (class "Default")
      (node (ref "PAD45") (pin "1") (pinfunction "P_1") (pintype "passive"))
    )
    (net (code "48") (name "unconnected-(PAD46-P-Pad1)") (class "Default")
      (node (ref "PAD46") (pin "1") (pinfunction "P_1") (pintype "passive"))
    )
    (net (code "49") (name "unconnected-(PAD47-P-Pad1)") (class "Default")
      (node (ref "PAD47") (pin "1") (pinfunction "P_1") (pintype "passive"))
    )
    (net (code "50") (name "unconnected-(PAD48-P-Pad1)") (class "Default")
      (node (ref "PAD48") (pin "1") (pinfunction "P_1") (pintype "passive"))
    )
    (net (code "51") (name "unconnected-(PAD49-P-Pad1)") (class "Default")
      (node (ref "PAD49") (pin "1") (pinfunction "P_1") (pintype "passive"))
    )
    (net (code "52") (name "unconnected-(PAD50-P-Pad1)") (class "Default")
      (node (ref "PAD50") (pin "1") (pinfunction "P_1") (pintype "passive"))
    )
    (net (code "53") (name "unconnected-(PAD51-P-Pad1)") (class "Default")
      (node (ref "PAD51") (pin "1") (pinfunction "P_1") (pintype "passive"))
    )
    (net (code "54") (name "unconnected-(PAD52-P-Pad1)") (class "Default")
      (node (ref "PAD52") (pin "1") (pinfunction "P_1") (pintype "passive"))
    )
    (net (code "55") (name "unconnected-(PAD53-P-Pad1)") (class "Default")
      (node (ref "PAD53") (pin "1") (pinfunction "P_1") (pintype "passive"))
    )
    (net (code "56") (name "unconnected-(PAD54-P-Pad1)") (class "Default")
      (node (ref "PAD54") (pin "1") (pinfunction "P_1") (pintype "passive"))
    )
    (net (code "57") (name "unconnected-(PAD55-P-Pad1)") (class "Default")
      (node (ref "PAD55") (pin "1") (pinfunction "P_1") (pintype "passive"))
    )
    (net (code "58") (name "unconnected-(PAD56-P-Pad1)") (class "Default")
      (node (ref "PAD56") (pin "1") (pinfunction "P_1") (pintype "passive"))
    )
    (net (code "59") (name "unconnected-(PAD57-P-Pad1)") (class "Default")
      (node (ref "PAD57") (pin "1") (pinfunction "P_1") (pintype "passive"))
    )
    (net (code "60") (name "unconnected-(PAD58-P-Pad1)") (class "Default")
      (node (ref "PAD58") (pin "1") (pinfunction "P_1") (pintype "passive"))
    )
    (net (code "61") (name "unconnected-(PAD59-P-Pad1)") (class "Default")
      (node (ref "PAD59") (pin "1") (pinfunction "P_1") (pintype "passive"))
    )
    (net (code "62") (name "unconnected-(PAD60-P-Pad1)") (class "Default")
      (node (ref "PAD60") (pin "1") (pinfunction "P_1") (pintype "passive"))
    )
    (net (code "63") (name "unconnected-(PAD61-P-Pad1)") (class "Default")
      (node (ref "PAD61") (pin "1") (pinfunction "P_1") (pintype "passive"))
    )
    (net (code "64") (name "unconnected-(PAD62-P-Pad1)") (class "Default")
      (node (ref "PAD62") (pin "1") (pinfunction "P_1") (pintype "passive"))
    )
    (net (code "65") (name "unconnected-(PAD63-P-Pad1)") (class "Default")
      (node (ref "PAD63") (pin "1") (pinfunction "P_1") (pintype "passive"))
    )
    (net (code "66") (name "unconnected-(PAD64-P-Pad1)") (class "Default")
      (node (ref "PAD64") (pin "1") (pinfunction "P_1") (pintype "passive"))
    )
    (net (code "67") (name "unconnected-(PAD65-P-Pad1)") (class "Default")
      (node (ref "PAD65") (pin "1") (pinfunction "P_1") (pintype "passive"))
    )
    (net (code "68") (name "unconnected-(PAD66-P-Pad1)") (class "Default")
      (node (ref "PAD66") (pin "1") (pinfunction "P_1") (pintype "passive"))
    )
    (net (code "69") (name "unconnected-(PAD67-P-Pad1)") (class "Default")
      (node (ref "PAD67") (pin "1") (pinfunction "P_1") (pintype "passive"))
    )
    (net (code "70") (name "unconnected-(PAD68-P-Pad1)") (class "Default")
      (node (ref "PAD68") (pin "1") (pinfunction "P_1") (pintype "passive"))
    )
    (net (code "71") (name "unconnected-(PAD69-P-Pad1)") (class "Default")
      (node (ref "PAD69") (pin "1") (pinfunction "P_1") (pintype "passive"))
    )
    (net (code "72") (name "unconnected-(PAD70-P-Pad1)") (class "Default")
      (node (ref "PAD70") (pin "1") (pinfunction "P_1") (pintype "passive"))
    )
    (net (code "73") (name "unconnected-(PAD71-P-Pad1)") (class "Default")
      (node (ref "PAD71") (pin "1") (pinfunction "P_1") (pintype "passive"))
    )
    (net (code "74") (name "unconnected-(PAD72-P-Pad1)") (class "Default")
      (node (ref "PAD72") (pin "1") (pinfunction "P_1") (pintype "passive"))
    )
    (net (code "75") (name "unconnected-(PAD97-P-Pad1)") (class "Default")
      (node (ref "PAD97") (pin "1") (pinfunction "P_1") (pintype "passive"))
    )
    (net (code "76") (name "unconnected-(PAD98-P-Pad1)") (class "Default")
      (node (ref "PAD98") (pin "1") (pinfunction "P_1") (pintype "passive"))
    )
    (net (code "77") (name "unconnected-(PAD99-P-Pad1)") (class "Default")
      (node (ref "PAD99") (pin "1") (pinfunction "P_1") (pintype "passive"))
    )
    (net (code "78") (name "unconnected-(PAD100-P-Pad1)") (class "Default")
      (node (ref "PAD100") (pin "1") (pinfunction "P_1") (pintype "passive"))
    )
    (net (code "79") (name "unconnected-(PAD101-P-Pad1)") (class "Default")
      (node (ref "PAD101") (pin "1") (pinfunction "P_1") (pintype "passive"))
    )
    (net (code "80") (name "unconnected-(PAD102-P-Pad1)") (class "Default")
      (node (ref "PAD102") (pin "1") (pinfunction "P_1") (pintype "passive"))
    )
    (net (code "81") (name "unconnected-(PAD103-P-Pad1)") (class "Default")
      (node (ref "PAD103") (pin "1") (pinfunction "P_1") (pintype "passive"))
    )
    (net (code "82") (name "unconnected-(PAD104-P-Pad1)") (class "Default")
      (node (ref "PAD104") (pin "1") (pinfunction "P_1") (pintype "passive"))
    )
    (net (code "83") (name "unconnected-(PAD105-P-Pad1)") (class "Default")
      (node (ref "PAD105") (pin "1") (pinfunction "P_1") (pintype "passive"))
    )
    (net (code "84") (name "unconnected-(PAD106-P-Pad1)") (class "Default")
      (node (ref "PAD106") (pin "1") (pinfunction "P_1") (pintype "passive"))
    )
    (net (code "85") (name "unconnected-(PAD107-P-Pad1)") (class "Default")
      (node (ref "PAD107") (pin "1") (pinfunction "P_1") (pintype "passive"))
    )
    (net (code "86") (name "unconnected-(PAD108-P-Pad1)") (class "Default")
      (node (ref "PAD108") (pin "1") (pinfunction "P_1") (pintype "passive"))
    )
    (net (code "87") (name "unconnected-(PAD109-P-Pad1)") (class "Default")
      (node (ref "PAD109") (pin "1") (pinfunction "P_1") (pintype "passive"))
    )
    (net (code "88") (name "unconnected-(PAD110-P-Pad1)") (class "Default")
      (node (ref "PAD110") (pin "1") (pinfunction "P_1") (pintype "passive"))
    )
    (net (code "89") (name "unconnected-(PAD111-P-Pad1)") (class "Default")
      (node (ref "PAD111") (pin "1") (pinfunction "P_1") (pintype "passive"))
    )
    (net (code "90") (name "unconnected-(PAD112-P-Pad1)") (class "Default")
      (node (ref "PAD112") (pin "1") (pinfunction "P_1") (pintype "passive"))
    )
    (net (code "91") (name "unconnected-(PAD113-P-Pad1)") (class "Default")
      (node (ref "PAD113") (pin "1") (pinfunction "P_1") (pintype "passive"))
    )
    (net (code "92") (name "unconnected-(PAD114-P-Pad1)") (class "Default")
      (node (ref "PAD114") (pin "1") (pinfunction "P_1") (pintype "passive"))
    )
    (net (code "93") (name "unconnected-(PAD115-P-Pad1)") (class "Default")
      (node (ref "PAD115") (pin "1") (pinfunction "P_1") (pintype "passive"))
    )
    (net (code "94") (name "unconnected-(PAD116-P-Pad1)") (class "Default")
      (node (ref "PAD116") (pin "1") (pinfunction "P_1") (pintype "passive"))
    )
    (net (code "95") (name "unconnected-(PAD117-P-Pad1)") (class "Default")
      (node (ref "PAD117") (pin "1") (pinfunction "P_1") (pintype "passive"))
    )
    (net (code "96") (name "unconnected-(PAD118-P-Pad1)") (class "Default")
      (node (ref "PAD118") (pin "1") (pinfunction "P_1") (pintype "passive"))
    )
    (net (code "97") (name "unconnected-(PAD119-P-Pad1)") (class "Default")
      (node (ref "PAD119") (pin "1") (pinfunction "P_1") (pintype "passive"))
    )
    (net (code "98") (name "unconnected-(PAD120-P-Pad1)") (class "Default")
      (node (ref "PAD120") (pin "1") (pinfunction "P_1") (pintype "passive"))
    )
    (net (code "99") (name "unconnected-(PAD121-P-Pad1)") (class "Default")
      (node (ref "PAD121") (pin "1") (pinfunction "P_1") (pintype "passive"))
    )
    (net (code "100") (name "unconnected-(PAD122-P-Pad1)") (class "Default")
      (node (ref "PAD122") (pin "1") (pinfunction "P_1") (pintype "passive"))
    )
    (net (code "101") (name "unconnected-(PAD123-P-Pad1)") (class "Default")
      (node (ref "PAD123") (pin "1") (pinfunction "P_1") (pintype "passive"))
    )
    (net (code "102") (name "unconnected-(PAD124-P-Pad1)") (class "Default")
      (node (ref "PAD124") (pin "1") (pinfunction "P_1") (pintype "passive"))
    )
    (net (code "103") (name "unconnected-(PAD125-P-Pad1)") (class "Default")
      (node (ref "PAD125") (pin "1") (pinfunction "P_1") (pintype "passive"))
    )
    (net (code "104") (name "unconnected-(PAD126-P-Pad1)") (class "Default")
      (node (ref "PAD126") (pin "1") (pinfunction "P_1") (pintype "passive"))
    )
    (net (code "105") (name "unconnected-(PAD127-P-Pad1)") (class "Default")
      (node (ref "PAD127") (pin "1") (pinfunction "P_1") (pintype "passive"))
    )
    (net (code "106") (name "unconnected-(PAD128-P-Pad1)") (class "Default")
      (node (ref "PAD128") (pin "1") (pinfunction "P_1") (pintype "passive"))
    )
    (net (code "107") (name "unconnected-(PAD129-P-Pad1)") (class "Default")
      (node (ref "PAD129") (pin "1") (pinfunction "P_1") (pintype "passive"))
    )
    (net (code "108") (name "unconnected-(PAD130-P-Pad1)") (class "Default")
      (node (ref "PAD130") (pin "1") (pinfunction "P_1") (pintype "passive"))
    )
    (net (code "109") (name "unconnected-(PAD131-P-Pad1)") (class "Default")
      (node (ref "PAD131") (pin "1") (pinfunction "P_1") (pintype "passive"))
    )
    (net (code "110") (name "unconnected-(PAD132-P-Pad1)") (class "Default")
      (node (ref "PAD132") (pin "1") (pinfunction "P_1") (pintype "passive"))
    )
    (net (code "111") (name "unconnected-(PAD133-P-Pad1)") (class "Default")
      (node (ref "PAD133") (pin "1") (pinfunction "P_1") (pintype "passive"))
    )
    (net (code "112") (name "unconnected-(PAD134-P-Pad1)") (class "Default")
      (node (ref "PAD134") (pin "1") (pinfunction "P_1") (pintype "passive"))
    )
    (net (code "113") (name "unconnected-(PAD135-P-Pad1)") (class "Default")
      (node (ref "PAD135") (pin "1") (pinfunction "P_1") (pintype "passive"))
    )
    (net (code "114") (name "unconnected-(PAD136-P-Pad1)") (class "Default")
      (node (ref "PAD136") (pin "1") (pinfunction "P_1") (pintype "passive"))
    )
    (net (code "115") (name "unconnected-(PAD137-P-Pad1)") (class "Default")
      (node (ref "PAD137") (pin "1") (pinfunction "P_1") (pintype "passive"))
    )
    (net (code "116") (name "unconnected-(PAD138-P-Pad1)") (class "Default")
      (node (ref "PAD138") (pin "1") (pinfunction "P_1") (pintype "passive"))
    )
    (net (code "117") (name "unconnected-(PAD139-P-Pad1)") (class "Default")
      (node (ref "PAD139") (pin "1") (pinfunction "P_1") (pintype "passive"))
    )
    (net (code "118") (name "unconnected-(PAD140-P-Pad1)") (class "Default")
      (node (ref "PAD140") (pin "1") (pinfunction "P_1") (pintype "passive"))
    )
    (net (code "119") (name "unconnected-(PAD141-P-Pad1)") (class "Default")
      (node (ref "PAD141") (pin "1") (pinfunction "P_1") (pintype "passive"))
    )
    (net (code "120") (name "unconnected-(PAD142-P-Pad1)") (class "Default")
      (node (ref "PAD142") (pin "1") (pinfunction "P_1") (pintype "passive"))
    )
    (net (code "121") (name "unconnected-(PAD143-P-Pad1)") (class "Default")
      (node (ref "PAD143") (pin "1") (pinfunction "P_1") (pintype "passive"))
    )
    (net (code "122") (name "unconnected-(PAD144-P-Pad1)") (class "Default")
      (node (ref "PAD144") (pin "1") (pinfunction "P_1") (pintype "passive"))
    )
    (net (code "123") (name "unconnected-(PAD145-P-Pad1)") (class "Default")
      (node (ref "PAD145") (pin "1") (pinfunction "P_1") (pintype "passive"))
    )
    (net (code "124") (name "unconnected-(PAD146-P-Pad1)") (class "Default")
      (node (ref "PAD146") (pin "1") (pinfunction "P_1") (pintype "passive"))
    )
    (net (code "125") (name "unconnected-(PAD147-P-Pad1)") (class "Default")
      (node (ref "PAD147") (pin "1") (pinfunction "P_1") (pintype "passive"))
    )
    (net (code "126") (name "unconnected-(PAD148-P-Pad1)") (class "Default")
      (node (ref "PAD148") (pin "1") (pinfunction "P_1") (pintype "passive"))
    )
    (net (code "127") (name "unconnected-(PAD149-P-Pad1)") (class "Default")
      (node (ref "PAD149") (pin "1") (pinfunction "P_1") (pintype "passive"))
    )
    (net (code "128") (name "unconnected-(PAD150-P-Pad1)") (class "Default")
      (node (ref "PAD150") (pin "1") (pinfunction "P_1") (pintype "passive"))
    )
    (net (code "129") (name "unconnected-(PAD151-P-Pad1)") (class "Default")
      (node (ref "PAD151") (pin "1") (pinfunction "P_1") (pintype "passive"))
    )
    (net (code "130") (name "unconnected-(PAD152-P-Pad1)") (class "Default")
      (node (ref "PAD152") (pin "1") (pinfunction "P_1") (pintype "passive"))
    )
    (net (code "131") (name "unconnected-(PAD153-P-Pad1)") (class "Default")
      (node (ref "PAD153") (pin "1") (pinfunction "P_1") (pintype "passive"))
    )
    (net (code "132") (name "unconnected-(PAD154-P-Pad1)") (class "Default")
      (node (ref "PAD154") (pin "1") (pinfunction "P_1") (pintype "passive"))
    )
    (net (code "133") (name "unconnected-(PAD155-P-Pad1)") (class "Default")
      (node (ref "PAD155") (pin "1") (pinfunction "P_1") (pintype "passive"))
    )
    (net (code "134") (name "unconnected-(PAD156-P-Pad1)") (class "Default")
      (node (ref "PAD156") (pin "1") (pinfunction "P_1") (pintype "passive"))
    )
    (net (code "135") (name "unconnected-(PAD157-P-Pad1)") (class "Default")
      (node (ref "PAD157") (pin "1") (pinfunction "P_1") (pintype "passive"))
    )
    (net (code "136") (name "unconnected-(PAD158-P-Pad1)") (class "Default")
      (node (ref "PAD158") (pin "1") (pinfunction "P_1") (pintype "passive"))
    )
    (net (code "137") (name "unconnected-(PAD159-P-Pad1)") (class "Default")
      (node (ref "PAD159") (pin "1") (pinfunction "P_1") (pintype "passive"))
    )
    (net (code "138") (name "unconnected-(PAD160-P-Pad1)") (class "Default")
      (node (ref "PAD160") (pin "1") (pinfunction "P_1") (pintype "passive"))
    )
    (net (code "139") (name "unconnected-(PAD161-P-Pad1)") (class "Default")
      (node (ref "PAD161") (pin "1") (pinfunction "P_1") (pintype "passive"))
    )
    (net (code "140") (name "unconnected-(PAD162-P-Pad1)") (class "Default")
      (node (ref "PAD162") (pin "1") (pinfunction "P_1") (pintype "passive"))
    )
    (net (code "141") (name "unconnected-(PAD163-P-Pad1)") (class "Default")
      (node (ref "PAD163") (pin "1") (pinfunction "P_1") (pintype "passive"))
    )
    (net (code "142") (name "unconnected-(PAD164-P-Pad1)") (class "Default")
      (node (ref "PAD164") (pin "1") (pinfunction "P_1") (pintype "passive"))
    )
    (net (code "143") (name "unconnected-(PAD165-P-Pad1)") (class "Default")
      (node (ref "PAD165") (pin "1") (pinfunction "P_1") (pintype "passive"))
    )
    (net (code "144") (name "unconnected-(PAD166-P-Pad1)") (class "Default")
      (node (ref "PAD166") (pin "1") (pinfunction "P_1") (pintype "passive"))
    )
    (net (code "145") (name "unconnected-(PAD167-P-Pad1)") (class "Default")
      (node (ref "PAD167") (pin "1") (pinfunction "P_1") (pintype "passive"))
    )
    (net (code "146") (name "unconnected-(PAD168-P-Pad1)") (class "Default")
      (node (ref "PAD168") (pin "1") (pinfunction "P_1") (pintype "passive"))
    )
    (net (code "147") (name "unconnected-(POWERA-O-Pad1)") (class "Default")
      (node (ref "POWER") (pin "1") (pinfunction "O_1") (pintype "passive"))
    )
    (net (code "148") (name "unconnected-(POWERA-P-Pad2)") (class "Default")
      (node (ref "POWER") (pin "2") (pinfunction "P_2") (pintype "passive"))
    )
  )
)
